# commonBoardPtV0_5-2014-11-05.net
KiCad netlist of a schematic drawn in EAGLE
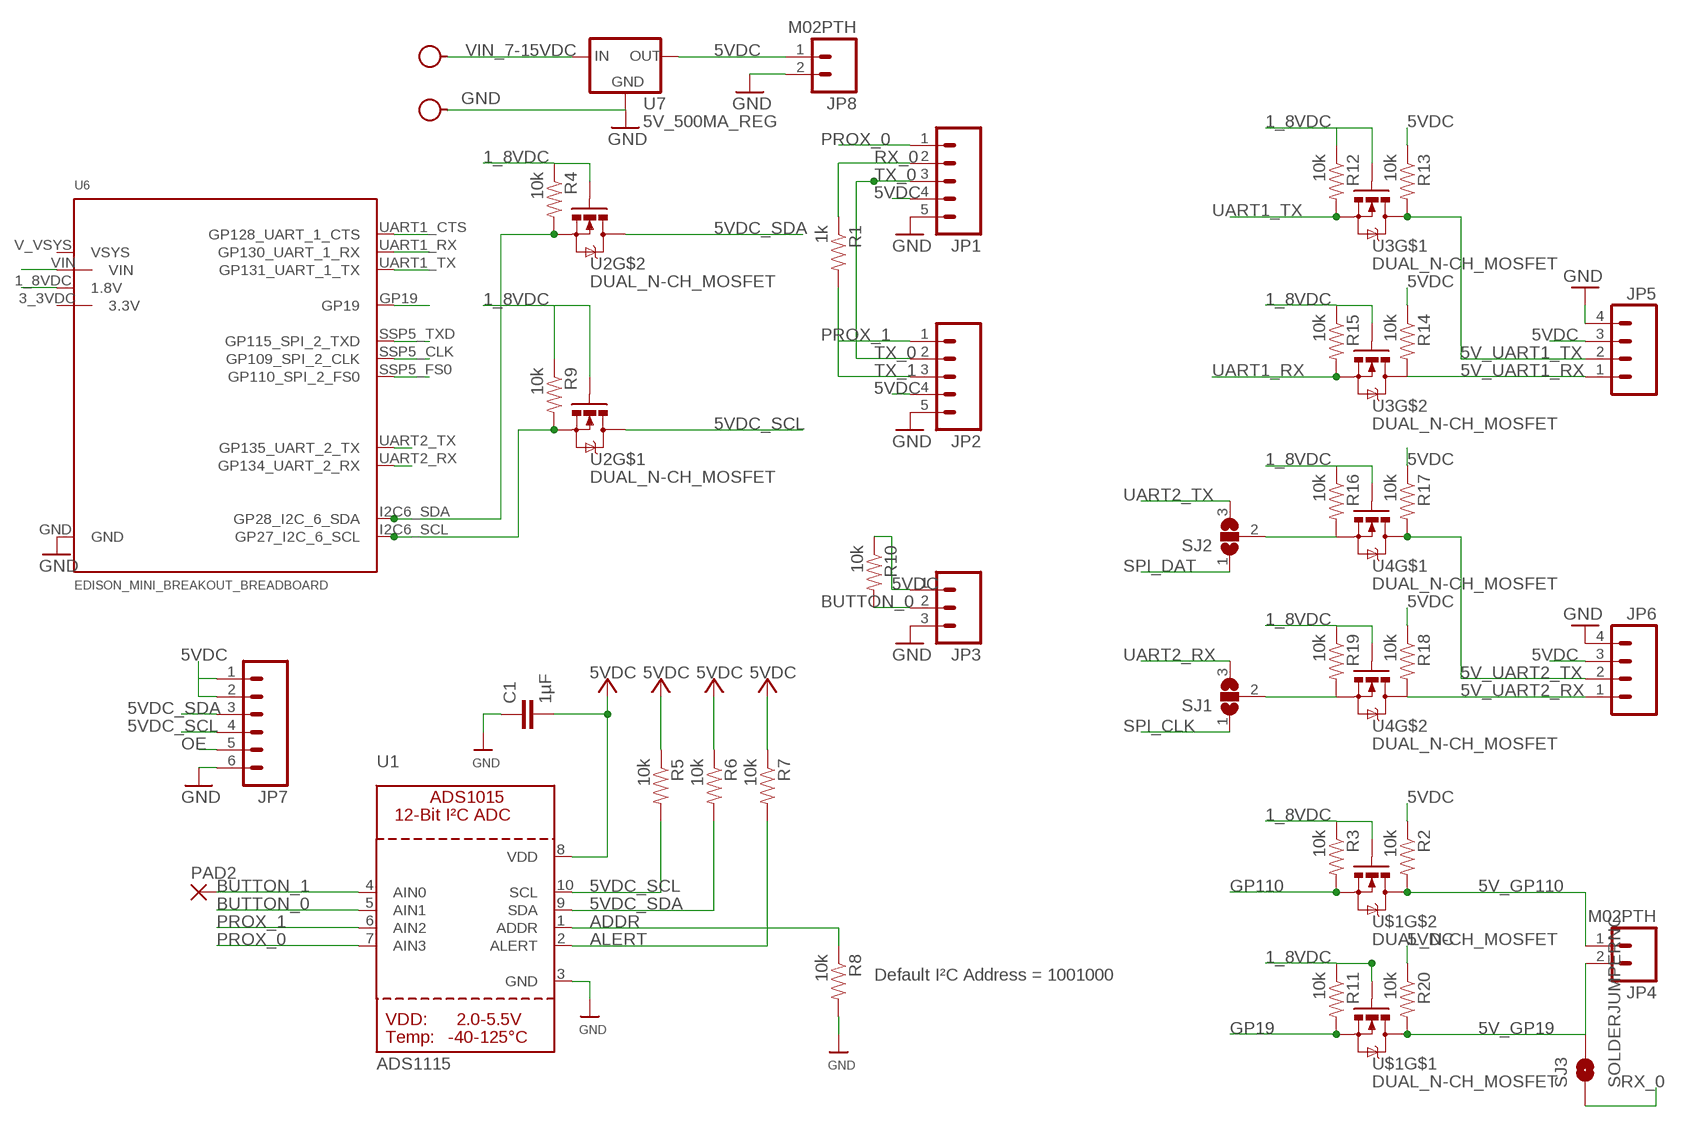
[diagram p0: schematic, sheet 1]

(export (version "E")
  (design (tool "Eeschema 10.0.6"))
  (components
    (comp (ref "C1")
      (value "1µF")
      (footprint "eagle-import:0603-CAP")
      (libsource (lib "eagle-import") (part "CAP0603-CAP"))
    )
    (comp (ref "GND")
      (value "SEW_HOLE-SMALL")
      (footprint "eagle-import:SIMPLE_HOLE_SM")
      (libsource (lib "eagle-import") (part "SEW_HOLE-SMALL"))
    )
    (comp (ref "JP1")
      (value "M05PTH")
      (footprint "eagle-import:1X05")
      (libsource (lib "eagle-import") (part "M05PTH"))
    )
    (comp (ref "JP2")
      (value "M05PTH")
      (footprint "eagle-import:1X05")
      (libsource (lib "eagle-import") (part "M05PTH"))
    )
    (comp (ref "JP3")
      (value "M03PTH")
      (footprint "eagle-import:1X03")
      (libsource (lib "eagle-import") (part "M03PTH"))
    )
    (comp (ref "JP4")
      (value "M02PTH")
      (footprint "eagle-import:1X02")
      (libsource (lib "eagle-import") (part "M02PTH"))
    )
    (comp (ref "JP5")
      (value "M04PTH")
      (footprint "eagle-import:1X04")
      (libsource (lib "eagle-import") (part "M04PTH"))
    )
    (comp (ref "JP6")
      (value "M04PTH")
      (footprint "eagle-import:1X04")
      (libsource (lib "eagle-import") (part "M04PTH"))
    )
    (comp (ref "JP7")
      (value "M06SIP")
      (footprint "eagle-import:1X06")
      (libsource (lib "eagle-import") (part "M06SIP"))
    )
    (comp (ref "JP8")
      (value "M02PTH")
      (footprint "eagle-import:1X02")
      (libsource (lib "eagle-import") (part "M02PTH"))
    )
    (comp (ref "PAD2")
      (value "2,15/1,0")
      (footprint "eagle-import:2,15_1,0")
      (libsource (lib "eagle-import") (part "2,15/1,0"))
    )
    (comp (ref "R1")
      (value "1k")
      (footprint "eagle-import:0603-RES")
      (libsource (lib "eagle-import") (part "RESISTOR0603-RES"))
    )
    (comp (ref "R2")
      (value "10k")
      (footprint "eagle-import:0603-RES")
      (libsource (lib "eagle-import") (part "RESISTOR0603-RES"))
    )
    (comp (ref "R3")
      (value "10k")
      (footprint "eagle-import:0603-RES")
      (libsource (lib "eagle-import") (part "RESISTOR0603-RES"))
    )
    (comp (ref "R4")
      (value "10k")
      (footprint "eagle-import:0603-RES")
      (libsource (lib "eagle-import") (part "RESISTOR0603-RES"))
    )
    (comp (ref "R5")
      (value "10k")
      (footprint "eagle-import:0603-RES")
      (libsource (lib "eagle-import") (part "RESISTOR0603-RES"))
    )
    (comp (ref "R6")
      (value "10k")
      (footprint "eagle-import:0603-RES")
      (libsource (lib "eagle-import") (part "RESISTOR0603-RES"))
    )
    (comp (ref "R7")
      (value "10k")
      (footprint "eagle-import:0603-RES")
      (libsource (lib "eagle-import") (part "RESISTOR0603-RES"))
    )
    (comp (ref "R8")
      (value "10k")
      (footprint "eagle-import:0603-RES")
      (libsource (lib "eagle-import") (part "RESISTOR0603-RES"))
    )
    (comp (ref "R9")
      (value "10k")
      (footprint "eagle-import:0603-RES")
      (libsource (lib "eagle-import") (part "RESISTOR0603-RES"))
    )
    (comp (ref "R10")
      (value "10k")
      (footprint "eagle-import:0603-RES")
      (libsource (lib "eagle-import") (part "RESISTOR0603-RES"))
    )
    (comp (ref "R11")
      (value "10k")
      (footprint "eagle-import:0603-RES")
      (libsource (lib "eagle-import") (part "RESISTOR0603-RES"))
    )
    (comp (ref "R12")
      (value "10k")
      (footprint "eagle-import:0603-RES")
      (libsource (lib "eagle-import") (part "RESISTOR0603-RES"))
    )
    (comp (ref "R13")
      (value "10k")
      (footprint "eagle-import:0603-RES")
      (libsource (lib "eagle-import") (part "RESISTOR0603-RES"))
    )
    (comp (ref "R14")
      (value "10k")
      (footprint "eagle-import:0603-RES")
      (libsource (lib "eagle-import") (part "RESISTOR0603-RES"))
    )
    (comp (ref "R15")
      (value "10k")
      (footprint "eagle-import:0603-RES")
      (libsource (lib "eagle-import") (part "RESISTOR0603-RES"))
    )
    (comp (ref "R16")
      (value "10k")
      (footprint "eagle-import:0603-RES")
      (libsource (lib "eagle-import") (part "RESISTOR0603-RES"))
    )
    (comp (ref "R17")
      (value "10k")
      (footprint "eagle-import:0603-RES")
      (libsource (lib "eagle-import") (part "RESISTOR0603-RES"))
    )
    (comp (ref "R18")
      (value "10k")
      (footprint "eagle-import:0603-RES")
      (libsource (lib "eagle-import") (part "RESISTOR0603-RES"))
    )
    (comp (ref "R19")
      (value "10k")
      (footprint "eagle-import:0603-RES")
      (libsource (lib "eagle-import") (part "RESISTOR0603-RES"))
    )
    (comp (ref "R20")
      (value "10k")
      (footprint "eagle-import:0603-RES")
      (libsource (lib "eagle-import") (part "RESISTOR0603-RES"))
    )
    (comp (ref "SJ1")
      (value "SJ2W")
      (footprint "eagle-import:SJ_2")
      (libsource (lib "eagle-import") (part "SJ2W"))
    )
    (comp (ref "SJ2")
      (value "SJ2W")
      (footprint "eagle-import:SJ_2")
      (libsource (lib "eagle-import") (part "SJ2W"))
    )
    (comp (ref "SJ3")
      (value "SOLDERJUMPERNC")
      (footprint "eagle-import:SJ_2S")
      (libsource (lib "eagle-import") (part "SOLDERJUMPERNC"))
    )
    (comp (ref "U$1")
      (value "DUAL_N-CH_MOSFET")
      (footprint "eagle-import:SOT363_DUAL_N_MOSFET")
      (libsource (lib "eagle-import") (part "DUAL_N-CH_MOSFET"))
    )
    (comp (ref "U1")
      (value "ADS1115")
      (footprint "eagle-import:MSOP10")
      (libsource (lib "eagle-import") (part "ADC_ADS1015"))
    )
    (comp (ref "U2")
      (value "DUAL_N-CH_MOSFET")
      (footprint "eagle-import:SOT363_DUAL_N_MOSFET")
      (libsource (lib "eagle-import") (part "DUAL_N-CH_MOSFET"))
    )
    (comp (ref "U3")
      (value "DUAL_N-CH_MOSFET")
      (footprint "eagle-import:SOT363_DUAL_N_MOSFET")
      (libsource (lib "eagle-import") (part "DUAL_N-CH_MOSFET"))
    )
    (comp (ref "U4")
      (value "DUAL_N-CH_MOSFET")
      (footprint "eagle-import:SOT363_DUAL_N_MOSFET")
      (libsource (lib "eagle-import") (part "DUAL_N-CH_MOSFET"))
    )
    (comp (ref "U6")
      (value "EDISON_MINI_BREAKOUT_BREADBOARD")
      (footprint "eagle-import:EDISON_MINI_BREAK_BREADBOARD")
      (libsource (lib "eagle-import") (part "EDISON_MINI_BREAKOUT_BREADBOARD"))
    )
    (comp (ref "U7")
      (value "5V_500MA_REG")
      (footprint "eagle-import:5V_500MA_REG")
      (libsource (lib "eagle-import") (part "5V_500MA_REG"))
    )
    (comp (ref "VIN_7-15VDC")
      (value "SEW_HOLE-SMALL")
      (footprint "eagle-import:SIMPLE_HOLE_SM")
      (libsource (lib "eagle-import") (part "SEW_HOLE-SMALL"))
    )
  )
  (nets
    (net (code "1") (name "/1_8VDC") (class "Default")
      (node (ref "R11") (pin "1") (pinfunction "1_1") (pintype "passive"))
      (node (ref "R12") (pin "1") (pinfunction "1_1") (pintype "passive"))
      (node (ref "R15") (pin "1") (pinfunction "1_1") (pintype "passive"))
      (node (ref "R16") (pin "1") (pinfunction "1_1") (pintype "passive"))
      (node (ref "R19") (pin "1") (pinfunction "1_1") (pintype "passive"))
      (node (ref "R3") (pin "1") (pinfunction "1_1") (pintype "passive"))
      (node (ref "R4") (pin "1") (pinfunction "1_1") (pintype "passive"))
      (node (ref "R9") (pin "1") (pinfunction "1_1") (pintype "passive"))
      (node (ref "U$1") (pin "2") (pinfunction "G_2") (pintype "passive"))
      (node (ref "U$1") (pin "5") (pinfunction "G_5") (pintype "passive"))
      (node (ref "U2") (pin "2") (pinfunction "G_2") (pintype "passive"))
      (node (ref "U2") (pin "5") (pinfunction "G_5") (pintype "passive"))
      (node (ref "U3") (pin "2") (pinfunction "G_2") (pintype "passive"))
      (node (ref "U3") (pin "5") (pinfunction "G_5") (pintype "passive"))
      (node (ref "U4") (pin "2") (pinfunction "G_2") (pintype "passive"))
      (node (ref "U4") (pin "5") (pinfunction "G_5") (pintype "passive"))
      (node (ref "U6") (pin "1_8VDC") (pinfunction "1.8V_1_8VDC") (pintype "bidirectional"))
    )
    (net (code "2") (name "/5VDC_SCL") (class "Default")
      (node (ref "JP7") (pin "4") (pinfunction "4_4") (pintype "passive"))
      (node (ref "R5") (pin "2") (pinfunction "2_2") (pintype "passive"))
      (node (ref "U1") (pin "10") (pinfunction "SCL_10") (pintype "bidirectional"))
      (node (ref "U2") (pin "3") (pinfunction "D_3") (pintype "passive"))
    )
    (net (code "3") (name "/5VDC_SDA") (class "Default")
      (node (ref "JP7") (pin "3") (pinfunction "3_3") (pintype "passive"))
      (node (ref "R6") (pin "2") (pinfunction "2_2") (pintype "passive"))
      (node (ref "U1") (pin "9") (pinfunction "SDA_9") (pintype "bidirectional"))
      (node (ref "U2") (pin "6") (pinfunction "D_6") (pintype "passive"))
    )
    (net (code "4") (name "/5V_GP19") (class "Default")
      (node (ref "JP4") (pin "2") (pinfunction "2_2") (pintype "passive"))
      (node (ref "R20") (pin "2") (pinfunction "2_2") (pintype "passive"))
      (node (ref "SJ3") (pin "2") (pinfunction "2_2") (pintype "passive"))
      (node (ref "U$1") (pin "3") (pinfunction "D_3") (pintype "passive"))
    )
    (net (code "5") (name "/5V_GP110") (class "Default")
      (node (ref "JP4") (pin "1") (pinfunction "1_1") (pintype "passive"))
      (node (ref "R2") (pin "2") (pinfunction "2_2") (pintype "passive"))
      (node (ref "U$1") (pin "6") (pinfunction "D_6") (pintype "passive"))
    )
    (net (code "6") (name "/5V_UART1_RX") (class "Default")
      (node (ref "JP5") (pin "1") (pinfunction "1_1") (pintype "passive"))
      (node (ref "R14") (pin "2") (pinfunction "2_2") (pintype "passive"))
      (node (ref "U3") (pin "6") (pinfunction "D_6") (pintype "passive"))
    )
    (net (code "7") (name "/5V_UART1_TX") (class "Default")
      (node (ref "JP5") (pin "2") (pinfunction "2_2") (pintype "passive"))
      (node (ref "R13") (pin "2") (pinfunction "2_2") (pintype "passive"))
      (node (ref "U3") (pin "3") (pinfunction "D_3") (pintype "passive"))
    )
    (net (code "8") (name "/5V_UART2_RX") (class "Default")
      (node (ref "JP6") (pin "1") (pinfunction "1_1") (pintype "passive"))
      (node (ref "R18") (pin "2") (pinfunction "2_2") (pintype "passive"))
      (node (ref "U4") (pin "6") (pinfunction "D_6") (pintype "passive"))
    )
    (net (code "9") (name "/5V_UART2_TX") (class "Default")
      (node (ref "JP6") (pin "2") (pinfunction "2_2") (pintype "passive"))
      (node (ref "R17") (pin "2") (pinfunction "2_2") (pintype "passive"))
      (node (ref "U4") (pin "3") (pinfunction "D_3") (pintype "passive"))
    )
    (net (code "10") (name "/ADDR") (class "Default")
      (node (ref "R8") (pin "1") (pinfunction "1_1") (pintype "passive"))
      (node (ref "U1") (pin "1") (pinfunction "ADDR_1") (pintype "bidirectional"))
    )
    (net (code "11") (name "/ALERT") (class "Default")
      (node (ref "R7") (pin "2") (pinfunction "2_2") (pintype "passive"))
      (node (ref "U1") (pin "2") (pinfunction "ALERT_2") (pintype "bidirectional"))
    )
    (net (code "12") (name "/BUTTON_0") (class "Default")
      (node (ref "JP3") (pin "2") (pinfunction "2_2") (pintype "passive"))
      (node (ref "R10") (pin "2") (pinfunction "2_2") (pintype "passive"))
      (node (ref "U1") (pin "5") (pinfunction "AIN1_5") (pintype "bidirectional"))
    )
    (net (code "13") (name "/BUTTON_1") (class "Default")
      (node (ref "PAD2") (pin "1") (pinfunction "P_1") (pintype "passive"))
      (node (ref "U1") (pin "4") (pinfunction "AIN0_4") (pintype "bidirectional"))
    )
    (net (code "14") (name "/GP19") (class "Default")
      (node (ref "R11") (pin "2") (pinfunction "2_2") (pintype "passive"))
      (node (ref "U$1") (pin "4") (pinfunction "S_4") (pintype "passive"))
      (node (ref "U6") (pin "GP19") (pinfunction "GP19_GP19") (pintype "bidirectional"))
    )
    (net (code "15") (name "/GP110") (class "Default")
      (node (ref "R3") (pin "2") (pinfunction "2_2") (pintype "passive"))
      (node (ref "U$1") (pin "1") (pinfunction "S_1") (pintype "passive"))
      (node (ref "U6") (pin "SSP5_FS0") (pinfunction "GP110_SPI_2_FS0_SSP5_FS0") (pintype "bidirectional"))
    )
    (net (code "16") (name "/OE") (class "Default")
      (node (ref "JP7") (pin "5") (pinfunction "5_5") (pintype "passive"))
    )
    (net (code "17") (name "/PROX_0") (class "Default")
      (node (ref "JP1") (pin "1") (pinfunction "1_1") (pintype "passive"))
      (node (ref "U1") (pin "7") (pinfunction "AIN3_7") (pintype "bidirectional"))
    )
    (net (code "18") (name "/PROX_1") (class "Default")
      (node (ref "JP2") (pin "1") (pinfunction "1_1") (pintype "passive"))
      (node (ref "U1") (pin "6") (pinfunction "AIN2_6") (pintype "bidirectional"))
    )
    (net (code "19") (name "/RX_0") (class "Default")
      (node (ref "JP1") (pin "2") (pinfunction "2_2") (pintype "passive"))
      (node (ref "R1") (pin "1") (pinfunction "1_1") (pintype "passive"))
      (node (ref "SJ3") (pin "1") (pinfunction "1_1") (pintype "passive"))
    )
    (net (code "20") (name "/SPI_CLK") (class "Default")
      (node (ref "SJ1") (pin "1") (pinfunction "1_1") (pintype "passive"))
      (node (ref "U6") (pin "SSP5_CLK") (pinfunction "GP109_SPI_2_CLK_SSP5_CLK") (pintype "bidirectional"))
    )
    (net (code "21") (name "/SPI_DAT") (class "Default")
      (node (ref "SJ2") (pin "1") (pinfunction "1_1") (pintype "passive"))
      (node (ref "U6") (pin "SSP5_TXD") (pinfunction "GP115_SPI_2_TXD_SSP5_TXD") (pintype "bidirectional"))
    )
    (net (code "22") (name "/TX_0") (class "Default")
      (node (ref "JP1") (pin "3") (pinfunction "3_3") (pintype "passive"))
      (node (ref "JP2") (pin "2") (pinfunction "2_2") (pintype "passive"))
    )
    (net (code "23") (name "/TX_1") (class "Default")
      (node (ref "JP2") (pin "3") (pinfunction "3_3") (pintype "passive"))
      (node (ref "R1") (pin "2") (pinfunction "2_2") (pintype "passive"))
    )
    (net (code "24") (name "/UART1_RX") (class "Default")
      (node (ref "R15") (pin "2") (pinfunction "2_2") (pintype "passive"))
      (node (ref "U3") (pin "1") (pinfunction "S_1") (pintype "passive"))
      (node (ref "U6") (pin "UART1_RX") (pinfunction "GP130_UART_1_RX_UART1_RX") (pintype "bidirectional"))
    )
    (net (code "25") (name "/UART1_TX") (class "Default")
      (node (ref "R12") (pin "2") (pinfunction "2_2") (pintype "passive"))
      (node (ref "U3") (pin "4") (pinfunction "S_4") (pintype "passive"))
      (node (ref "U6") (pin "UART1_TX") (pinfunction "GP131_UART_1_TX_UART1_TX") (pintype "bidirectional"))
    )
    (net (code "26") (name "/UART2_RX") (class "Default")
      (node (ref "SJ1") (pin "3") (pinfunction "3_3") (pintype "passive"))
      (node (ref "U6") (pin "UART2_RX") (pinfunction "GP134_UART_2_RX_UART2_RX") (pintype "bidirectional"))
    )
    (net (code "27") (name "/UART2_TX") (class "Default")
      (node (ref "SJ2") (pin "3") (pinfunction "3_3") (pintype "passive"))
      (node (ref "U6") (pin "UART2_TX") (pinfunction "GP135_UART_2_TX_UART2_TX") (pintype "bidirectional"))
    )
    (net (code "28") (name "/VIN_7-15VDC") (class "Default")
      (node (ref "U6") (pin "VIN") (pinfunction "VIN_VIN") (pintype "bidirectional"))
      (node (ref "U7") (pin "IN") (pinfunction "IN_IN") (pintype "input"))
      (node (ref "VIN_7-15VDC") (pin "P$1") (pinfunction "P$1_P$1") (pintype "bidirectional"))
    )
    (net (code "29") (name "GND") (class "Default")
      (node (ref "C1") (pin "1") (pinfunction "1_1") (pintype "passive"))
      (node (ref "GND") (pin "P$1") (pinfunction "P$1_P$1") (pintype "bidirectional"))
      (node (ref "JP1") (pin "5") (pinfunction "5_5") (pintype "passive"))
      (node (ref "JP2") (pin "5") (pinfunction "5_5") (pintype "passive"))
      (node (ref "JP3") (pin "3") (pinfunction "3_3") (pintype "passive"))
      (node (ref "JP5") (pin "4") (pinfunction "4_4") (pintype "passive"))
      (node (ref "JP6") (pin "4") (pinfunction "4_4") (pintype "passive"))
      (node (ref "JP7") (pin "6") (pinfunction "6_6") (pintype "passive"))
      (node (ref "JP8") (pin "2") (pinfunction "2_2") (pintype "passive"))
      (node (ref "R8") (pin "2") (pinfunction "2_2") (pintype "passive"))
      (node (ref "U1") (pin "3") (pinfunction "GND_3") (pintype "bidirectional"))
      (node (ref "U6") (pin "GND") (pinfunction "GND_GND") (pintype "bidirectional"))
      (node (ref "U7") (pin "GND") (pinfunction "GND_GND") (pintype "input"))
    )
    (net (code "30") (name "Net-(U2A-S)") (class "Default")
      (node (ref "R9") (pin "2") (pinfunction "2_2") (pintype "passive"))
      (node (ref "U2") (pin "4") (pinfunction "S_4") (pintype "passive"))
      (node (ref "U6") (pin "I2C6_SCL") (pinfunction "GP27_I2C_6_SCL_I2C6_SCL") (pintype "bidirectional"))
    )
    (net (code "31") (name "Net-(U2B-S)") (class "Default")
      (node (ref "R4") (pin "2") (pinfunction "2_2") (pintype "passive"))
      (node (ref "U2") (pin "1") (pinfunction "S_1") (pintype "passive"))
      (node (ref "U6") (pin "I2C6_SDA") (pinfunction "GP28_I2C_6_SDA_I2C6_SDA") (pintype "bidirectional"))
    )
    (net (code "32") (name "Net-(U4A-S)") (class "Default")
      (node (ref "R16") (pin "2") (pinfunction "2_2") (pintype "passive"))
      (node (ref "SJ2") (pin "2") (pinfunction "2_2") (pintype "passive"))
      (node (ref "U4") (pin "4") (pinfunction "S_4") (pintype "passive"))
    )
    (net (code "33") (name "Net-(U4B-S)") (class "Default")
      (node (ref "R19") (pin "2") (pinfunction "2_2") (pintype "passive"))
      (node (ref "SJ1") (pin "2") (pinfunction "2_2") (pintype "passive"))
      (node (ref "U4") (pin "1") (pinfunction "S_1") (pintype "passive"))
    )
    (net (code "34") (name "VDD") (class "Default")
      (node (ref "C1") (pin "2") (pinfunction "2_2") (pintype "passive"))
      (node (ref "JP1") (pin "4") (pinfunction "4_4") (pintype "passive"))
      (node (ref "JP2") (pin "4") (pinfunction "4_4") (pintype "passive"))
      (node (ref "JP3") (pin "1") (pinfunction "1_1") (pintype "passive"))
      (node (ref "JP5") (pin "3") (pinfunction "3_3") (pintype "passive"))
      (node (ref "JP6") (pin "3") (pinfunction "3_3") (pintype "passive"))
      (node (ref "JP7") (pin "1") (pinfunction "1_1") (pintype "passive"))
      (node (ref "JP7") (pin "2") (pinfunction "2_2") (pintype "passive"))
      (node (ref "JP8") (pin "1") (pinfunction "1_1") (pintype "passive"))
      (node (ref "R10") (pin "1") (pinfunction "1_1") (pintype "passive"))
      (node (ref "R13") (pin "1") (pinfunction "1_1") (pintype "passive"))
      (node (ref "R14") (pin "1") (pinfunction "1_1") (pintype "passive"))
      (node (ref "R17") (pin "1") (pinfunction "1_1") (pintype "passive"))
      (node (ref "R18") (pin "1") (pinfunction "1_1") (pintype "passive"))
      (node (ref "R2") (pin "1") (pinfunction "1_1") (pintype "passive"))
      (node (ref "R20") (pin "1") (pinfunction "1_1") (pintype "passive"))
      (node (ref "R5") (pin "1") (pinfunction "1_1") (pintype "passive"))
      (node (ref "R6") (pin "1") (pinfunction "1_1") (pintype "passive"))
      (node (ref "R7") (pin "1") (pinfunction "1_1") (pintype "passive"))
      (node (ref "U1") (pin "8") (pinfunction "VDD_8") (pintype "bidirectional"))
      (node (ref "U7") (pin "OUT") (pinfunction "OUT_OUT") (pintype "output"))
    )
    (net (code "35") (name "unconnected-(U6-3.3V-Pad3_3VDC)") (class "Default")
      (node (ref "U6") (pin "3_3VDC") (pinfunction "3.3V_3_3VDC") (pintype "bidirectional"))
    )
    (net (code "36") (name "unconnected-(U6-GP128_UART_1_CTS-PadUART1_CTS)") (class "Default")
      (node (ref "U6") (pin "UART1_CTS") (pinfunction "GP128_UART_1_CTS_UART1_CTS") (pintype "bidirectional"))
    )
    (net (code "37") (name "unconnected-(U6-VSYS-PadV_VSYS)") (class "Default")
      (node (ref "U6") (pin "V_VSYS") (pinfunction "VSYS_V_VSYS") (pintype "bidirectional"))
    )
  )
)
